# MSP432.net
KiCad netlist of a schematic drawn in Altium Designer
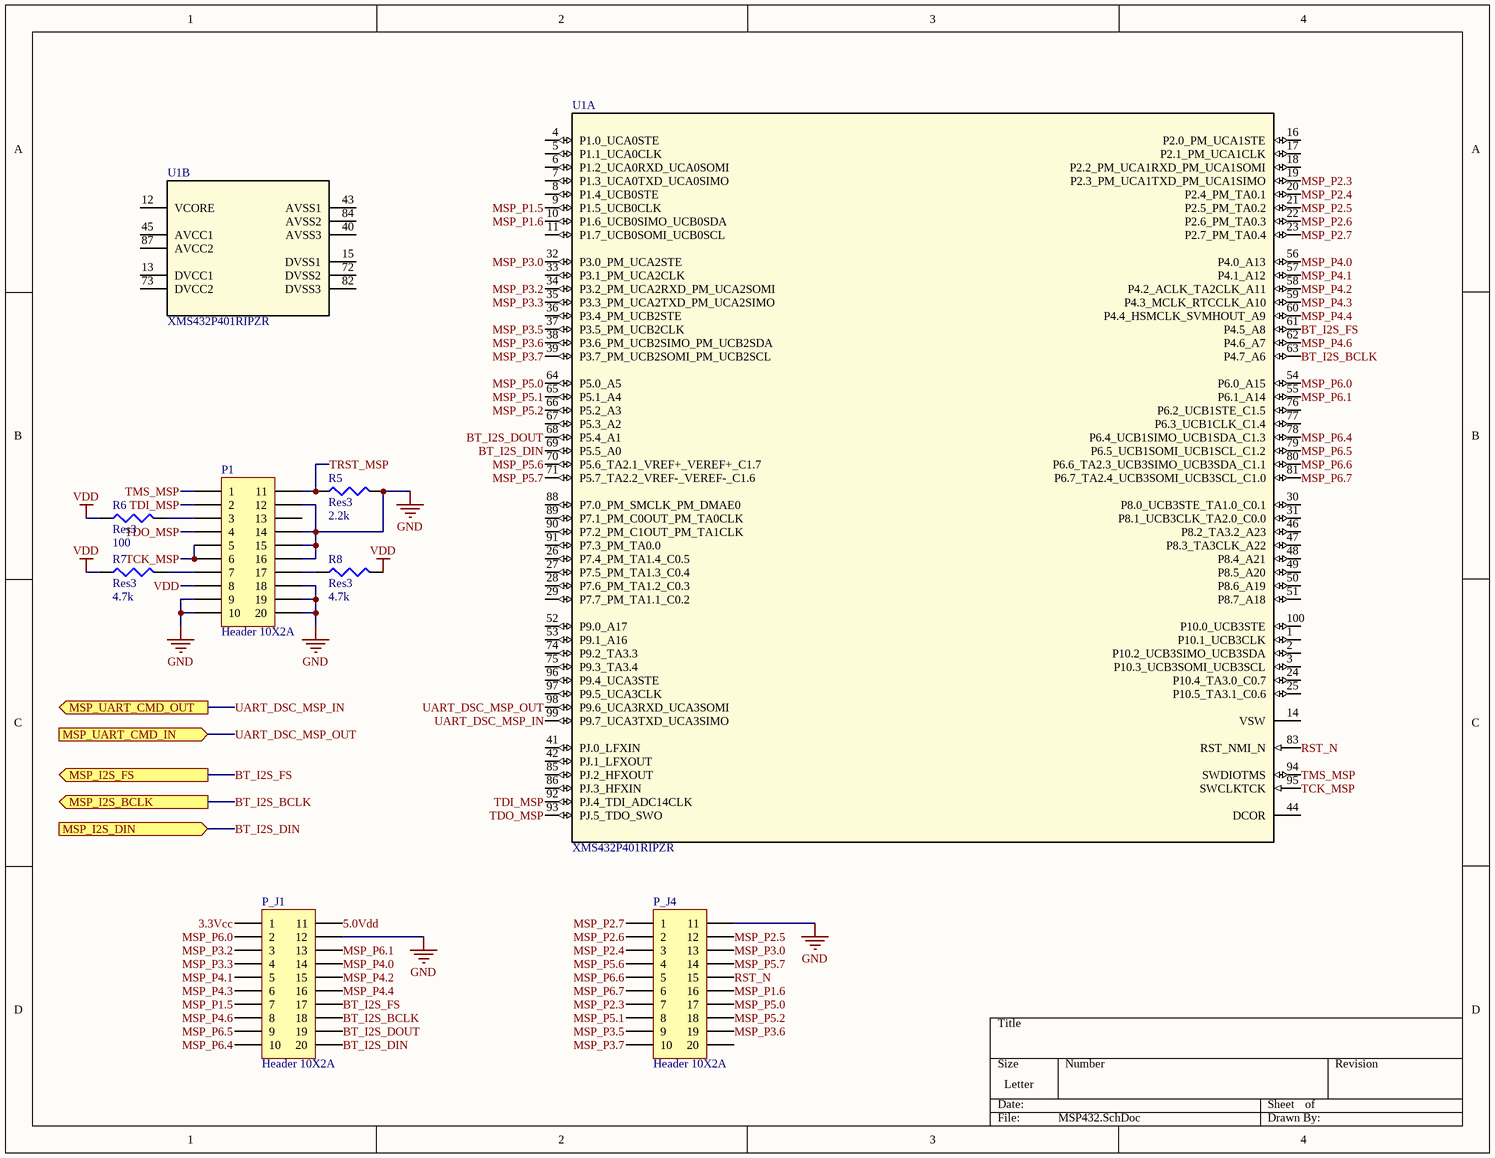
[diagram p0: MSP432.SchDoc]

(export (version "E")
  (design (tool "Eeschema 10.0.6"))
  (components
    (comp (ref "P1")
      (value "Header 10X2A")
      (footprint "HDR2X10_CEN")
      (description "Header, 10-Pin, Dual row")
      (fields (field (name "PUBLISHER") "Altium Limited"))
      (libsource (lib "Miscellaneous Connectors") (part "Header 10X2A"))
    )
    (comp (ref "P_J1")
      (value "Header 10X2A")
      (footprint "HDR2X10_CEN")
      (description "Header, 10-Pin, Dual row")
      (fields (field (name "PUBLISHER") "Altium Limited"))
      (libsource (lib "Miscellaneous Connectors") (part "Header 10X2A"))
    )
    (comp (ref "P_J4")
      (value "Header 10X2A")
      (footprint "HDR2X10_CEN")
      (description "Header, 10-Pin, Dual row")
      (fields (field (name "PUBLISHER") "Altium Limited"))
      (libsource (lib "Miscellaneous Connectors") (part "Header 10X2A"))
    )
    (comp (ref "R5")
      (value "Res3")
      (footprint "J1-0603")
      (description "Resistor")
      (fields (field (name "ALTIUM_VALUE") "2.2k") (field (name "PUBLISHER") "Altium Limited"))
      (libsource (lib "Miscellaneous Devices") (part "Res3"))
    )
    (comp (ref "R6")
      (value "Res3")
      (footprint "J1-0603")
      (description "Resistor")
      (fields (field (name "ALTIUM_VALUE") "100") (field (name "PUBLISHER") "Altium Limited"))
      (libsource (lib "Miscellaneous Devices") (part "Res3"))
    )
    (comp (ref "R7")
      (value "Res3")
      (footprint "J1-0603")
      (description "Resistor")
      (fields (field (name "ALTIUM_VALUE") "4.7k") (field (name "PUBLISHER") "Altium Limited"))
      (libsource (lib "Miscellaneous Devices") (part "Res3"))
    )
    (comp (ref "R8")
      (value "Res3")
      (footprint "J1-0603")
      (description "Resistor")
      (fields (field (name "ALTIUM_VALUE") "4.7k") (field (name "PUBLISHER") "Altium Limited"))
      (libsource (lib "Miscellaneous Devices") (part "Res3"))
    )
    (comp (ref "U1")
      (value "XMS432P401RIPZR")
      (footprint "PZ0100A_N")
      (description "Imported")
      (fields (field (name "MANUFACTURER") "Texas Instruments"))
      (libsource (lib "XMS432P401R") (part "XMS432P401RIPZR"))
    )
  )
  (nets
    (net (code "1") (name "/3.3Vcc") (class "Default")
      (node (ref "P_J1") (pin "1") (pinfunction "1_1") (pintype "passive"))
    )
    (net (code "2") (name "/5.0Vdd") (class "Default")
      (node (ref "P_J1") (pin "11") (pinfunction "11_11") (pintype "passive"))
    )
    (net (code "3") (name "/BT_I2S_BCLK") (class "Default")
      (node (ref "P_J1") (pin "18") (pinfunction "18_18") (pintype "passive"))
      (node (ref "U1") (pin "63") (pinfunction "P4.7_A6_63") (pintype "bidirectional"))
    )
    (net (code "4") (name "/BT_I2S_DIN") (class "Default")
      (node (ref "P_J1") (pin "20") (pinfunction "20_20") (pintype "passive"))
      (node (ref "U1") (pin "69") (pinfunction "P5.5_A0_69") (pintype "bidirectional"))
    )
    (net (code "5") (name "/BT_I2S_DOUT") (class "Default")
      (node (ref "P_J1") (pin "19") (pinfunction "19_19") (pintype "passive"))
      (node (ref "U1") (pin "68") (pinfunction "P5.4_A1_68") (pintype "bidirectional"))
    )
    (net (code "6") (name "/BT_I2S_FS") (class "Default")
      (node (ref "P_J1") (pin "17") (pinfunction "17_17") (pintype "passive"))
      (node (ref "U1") (pin "61") (pinfunction "P4.5_A8_61") (pintype "bidirectional"))
    )
    (net (code "7") (name "/MSP_P1.5") (class "Default")
      (node (ref "P_J1") (pin "7") (pinfunction "7_7") (pintype "passive"))
      (node (ref "U1") (pin "9") (pinfunction "P1.5_UCB0CLK_9") (pintype "bidirectional"))
    )
    (net (code "8") (name "/MSP_P1.6") (class "Default")
      (node (ref "P_J4") (pin "16") (pinfunction "16_16") (pintype "passive"))
      (node (ref "U1") (pin "10") (pinfunction "P1.6_UCB0SIMO_UCB0SDA_10") (pintype "bidirectional"))
    )
    (net (code "9") (name "/MSP_P2.3") (class "Default")
      (node (ref "P_J4") (pin "7") (pinfunction "7_7") (pintype "passive"))
      (node (ref "U1") (pin "19") (pinfunction "P2.3_PM_UCA1TXD_PM_UCA1SIMO_19") (pintype "bidirectional"))
    )
    (net (code "10") (name "/MSP_P2.4") (class "Default")
      (node (ref "P_J4") (pin "3") (pinfunction "3_3") (pintype "passive"))
      (node (ref "U1") (pin "20") (pinfunction "P2.4_PM_TA0.1_20") (pintype "bidirectional"))
    )
    (net (code "11") (name "/MSP_P2.5") (class "Default")
      (node (ref "P_J4") (pin "12") (pinfunction "12_12") (pintype "passive"))
      (node (ref "U1") (pin "21") (pinfunction "P2.5_PM_TA0.2_21") (pintype "bidirectional"))
    )
    (net (code "12") (name "/MSP_P2.6") (class "Default")
      (node (ref "P_J4") (pin "2") (pinfunction "2_2") (pintype "passive"))
      (node (ref "U1") (pin "22") (pinfunction "P2.6_PM_TA0.3_22") (pintype "bidirectional"))
    )
    (net (code "13") (name "/MSP_P2.7") (class "Default")
      (node (ref "P_J4") (pin "1") (pinfunction "1_1") (pintype "passive"))
      (node (ref "U1") (pin "23") (pinfunction "P2.7_PM_TA0.4_23") (pintype "bidirectional"))
    )
    (net (code "14") (name "/MSP_P3.0") (class "Default")
      (node (ref "P_J4") (pin "13") (pinfunction "13_13") (pintype "passive"))
      (node (ref "U1") (pin "32") (pinfunction "P3.0_PM_UCA2STE_32") (pintype "bidirectional"))
    )
    (net (code "15") (name "/MSP_P3.2") (class "Default")
      (node (ref "P_J1") (pin "3") (pinfunction "3_3") (pintype "passive"))
      (node (ref "U1") (pin "34") (pinfunction "P3.2_PM_UCA2RXD_PM_UCA2SOMI_34") (pintype "bidirectional"))
    )
    (net (code "16") (name "/MSP_P3.3") (class "Default")
      (node (ref "P_J1") (pin "4") (pinfunction "4_4") (pintype "passive"))
      (node (ref "U1") (pin "35") (pinfunction "P3.3_PM_UCA2TXD_PM_UCA2SIMO_35") (pintype "bidirectional"))
    )
    (net (code "17") (name "/MSP_P3.5") (class "Default")
      (node (ref "P_J4") (pin "9") (pinfunction "9_9") (pintype "passive"))
      (node (ref "U1") (pin "37") (pinfunction "P3.5_PM_UCB2CLK_37") (pintype "bidirectional"))
    )
    (net (code "18") (name "/MSP_P3.6") (class "Default")
      (node (ref "P_J4") (pin "19") (pinfunction "19_19") (pintype "passive"))
      (node (ref "U1") (pin "38") (pinfunction "P3.6_PM_UCB2SIMO_PM_UCB2SDA_38") (pintype "bidirectional"))
    )
    (net (code "19") (name "/MSP_P3.7") (class "Default")
      (node (ref "P_J4") (pin "10") (pinfunction "10_10") (pintype "passive"))
      (node (ref "U1") (pin "39") (pinfunction "P3.7_PM_UCB2SOMI_PM_UCB2SCL_39") (pintype "bidirectional"))
    )
    (net (code "20") (name "/MSP_P4.0") (class "Default")
      (node (ref "P_J1") (pin "14") (pinfunction "14_14") (pintype "passive"))
      (node (ref "U1") (pin "56") (pinfunction "P4.0_A13_56") (pintype "bidirectional"))
    )
    (net (code "21") (name "/MSP_P4.1") (class "Default")
      (node (ref "P_J1") (pin "5") (pinfunction "5_5") (pintype "passive"))
      (node (ref "U1") (pin "57") (pinfunction "P4.1_A12_57") (pintype "bidirectional"))
    )
    (net (code "22") (name "/MSP_P4.2") (class "Default")
      (node (ref "P_J1") (pin "15") (pinfunction "15_15") (pintype "passive"))
      (node (ref "U1") (pin "58") (pinfunction "P4.2_ACLK_TA2CLK_A11_58") (pintype "bidirectional"))
    )
    (net (code "23") (name "/MSP_P4.3") (class "Default")
      (node (ref "P_J1") (pin "6") (pinfunction "6_6") (pintype "passive"))
      (node (ref "U1") (pin "59") (pinfunction "P4.3_MCLK_RTCCLK_A10_59") (pintype "bidirectional"))
    )
    (net (code "24") (name "/MSP_P4.4") (class "Default")
      (node (ref "P_J1") (pin "16") (pinfunction "16_16") (pintype "passive"))
      (node (ref "U1") (pin "60") (pinfunction "P4.4_HSMCLK_SVMHOUT_A9_60") (pintype "bidirectional"))
    )
    (net (code "25") (name "/MSP_P4.6") (class "Default")
      (node (ref "P_J1") (pin "8") (pinfunction "8_8") (pintype "passive"))
      (node (ref "U1") (pin "62") (pinfunction "P4.6_A7_62") (pintype "bidirectional"))
    )
    (net (code "26") (name "/MSP_P5.0") (class "Default")
      (node (ref "P_J4") (pin "17") (pinfunction "17_17") (pintype "passive"))
      (node (ref "U1") (pin "64") (pinfunction "P5.0_A5_64") (pintype "bidirectional"))
    )
    (net (code "27") (name "/MSP_P5.1") (class "Default")
      (node (ref "P_J4") (pin "8") (pinfunction "8_8") (pintype "passive"))
      (node (ref "U1") (pin "65") (pinfunction "P5.1_A4_65") (pintype "bidirectional"))
    )
    (net (code "28") (name "/MSP_P5.2") (class "Default")
      (node (ref "P_J4") (pin "18") (pinfunction "18_18") (pintype "passive"))
      (node (ref "U1") (pin "66") (pinfunction "P5.2_A3_66") (pintype "bidirectional"))
    )
    (net (code "29") (name "/MSP_P5.6") (class "Default")
      (node (ref "P_J4") (pin "4") (pinfunction "4_4") (pintype "passive"))
      (node (ref "U1") (pin "70") (pinfunction "P5.6_TA2.1_VREF+_VEREF+_C1.7_70") (pintype "bidirectional"))
    )
    (net (code "30") (name "/MSP_P5.7") (class "Default")
      (node (ref "P_J4") (pin "14") (pinfunction "14_14") (pintype "passive"))
      (node (ref "U1") (pin "71") (pinfunction "P5.7_TA2.2_VREF-_VEREF-_C1.6_71") (pintype "bidirectional"))
    )
    (net (code "31") (name "/MSP_P6.0") (class "Default")
      (node (ref "P_J1") (pin "2") (pinfunction "2_2") (pintype "passive"))
      (node (ref "U1") (pin "54") (pinfunction "P6.0_A15_54") (pintype "bidirectional"))
    )
    (net (code "32") (name "/MSP_P6.1") (class "Default")
      (node (ref "P_J1") (pin "13") (pinfunction "13_13") (pintype "passive"))
      (node (ref "U1") (pin "55") (pinfunction "P6.1_A14_55") (pintype "bidirectional"))
    )
    (net (code "33") (name "/MSP_P6.4") (class "Default")
      (node (ref "P_J1") (pin "10") (pinfunction "10_10") (pintype "passive"))
      (node (ref "U1") (pin "78") (pinfunction "P6.4_UCB1SIMO_UCB1SDA_C1.3_78") (pintype "bidirectional"))
    )
    (net (code "34") (name "/MSP_P6.5") (class "Default")
      (node (ref "P_J1") (pin "9") (pinfunction "9_9") (pintype "passive"))
      (node (ref "U1") (pin "79") (pinfunction "P6.5_UCB1SOMI_UCB1SCL_C1.2_79") (pintype "bidirectional"))
    )
    (net (code "35") (name "/MSP_P6.6") (class "Default")
      (node (ref "P_J4") (pin "5") (pinfunction "5_5") (pintype "passive"))
      (node (ref "U1") (pin "80") (pinfunction "P6.6_TA2.3_UCB3SIMO_UCB3SDA_C1.1_80") (pintype "bidirectional"))
    )
    (net (code "36") (name "/MSP_P6.7") (class "Default")
      (node (ref "P_J4") (pin "6") (pinfunction "6_6") (pintype "passive"))
      (node (ref "U1") (pin "81") (pinfunction "P6.7_TA2.4_UCB3SOMI_UCB3SCL_C1.0_81") (pintype "bidirectional"))
    )
    (net (code "37") (name "/RST_N") (class "Default")
      (node (ref "P_J4") (pin "15") (pinfunction "15_15") (pintype "passive"))
      (node (ref "U1") (pin "83") (pinfunction "RST_NMI_N_83") (pintype "input"))
    )
    (net (code "38") (name "/TCK_MSP") (class "Default")
      (node (ref "P1") (pin "5") (pinfunction "5_5") (pintype "passive"))
      (node (ref "P1") (pin "6") (pinfunction "6_6") (pintype "passive"))
      (node (ref "U1") (pin "95") (pinfunction "SWCLKTCK_95") (pintype "input"))
    )
    (net (code "39") (name "/TDI_MSP") (class "Default")
      (node (ref "P1") (pin "2") (pinfunction "2_2") (pintype "passive"))
      (node (ref "U1") (pin "92") (pinfunction "PJ.4_TDI_ADC14CLK_92") (pintype "bidirectional"))
    )
    (net (code "40") (name "/TDO_MSP") (class "Default")
      (node (ref "P1") (pin "4") (pinfunction "4_4") (pintype "passive"))
      (node (ref "U1") (pin "93") (pinfunction "PJ.5_TDO_SWO_93") (pintype "bidirectional"))
    )
    (net (code "41") (name "/TMS_MSP") (class "Default")
      (node (ref "P1") (pin "1") (pinfunction "1_1") (pintype "passive"))
      (node (ref "U1") (pin "94") (pinfunction "SWDIOTMS_94") (pintype "bidirectional"))
    )
    (net (code "42") (name "/TRST_MSP") (class "Default")
      (node (ref "P1") (pin "11") (pinfunction "11_11") (pintype "passive"))
      (node (ref "R5") (pin "1") (pinfunction "1_1") (pintype "passive"))
    )
    (net (code "43") (name "/UART_DSC_MSP_IN") (class "Default")
      (node (ref "U1") (pin "99") (pinfunction "P9.7_UCA3TXD_UCA3SIMO_99") (pintype "bidirectional"))
    )
    (net (code "44") (name "/UART_DSC_MSP_OUT") (class "Default")
      (node (ref "U1") (pin "98") (pinfunction "P9.6_UCA3RXD_UCA3SOMI_98") (pintype "bidirectional"))
    )
    (net (code "45") (name "GND") (class "Default")
      (node (ref "P1") (pin "10") (pinfunction "10_10") (pintype "passive"))
      (node (ref "P1") (pin "12") (pinfunction "12_12") (pintype "passive"))
      (node (ref "P1") (pin "14") (pinfunction "14_14") (pintype "passive"))
      (node (ref "P1") (pin "15") (pinfunction "15_15") (pintype "passive"))
      (node (ref "P1") (pin "16") (pinfunction "16_16") (pintype "passive"))
      (node (ref "P1") (pin "18") (pinfunction "18_18") (pintype "passive"))
      (node (ref "P1") (pin "19") (pinfunction "19_19") (pintype "passive"))
      (node (ref "P1") (pin "20") (pinfunction "20_20") (pintype "passive"))
      (node (ref "P1") (pin "9") (pinfunction "9_9") (pintype "passive"))
      (node (ref "P_J1") (pin "12") (pinfunction "12_12") (pintype "passive"))
      (node (ref "P_J4") (pin "11") (pinfunction "11_11") (pintype "passive"))
      (node (ref "R5") (pin "2") (pinfunction "2_2") (pintype "passive"))
    )
    (net (code "46") (name "Net-(P1-Pad3)") (class "Default")
      (node (ref "P1") (pin "3") (pinfunction "3_3") (pintype "passive"))
      (node (ref "R6") (pin "2") (pinfunction "2_2") (pintype "passive"))
    )
    (net (code "47") (name "Net-(P1-Pad7)") (class "Default")
      (node (ref "P1") (pin "7") (pinfunction "7_7") (pintype "passive"))
      (node (ref "R7") (pin "2") (pinfunction "2_2") (pintype "passive"))
    )
    (net (code "48") (name "Net-(P1-Pad17)") (class "Default")
      (node (ref "P1") (pin "17") (pinfunction "17_17") (pintype "passive"))
      (node (ref "R8") (pin "1") (pinfunction "1_1") (pintype "passive"))
    )
    (net (code "49") (name "VDD") (class "Default")
      (node (ref "P1") (pin "8") (pinfunction "8_8") (pintype "passive"))
      (node (ref "R6") (pin "1") (pinfunction "1_1") (pintype "passive"))
      (node (ref "R7") (pin "1") (pinfunction "1_1") (pintype "passive"))
      (node (ref "R8") (pin "2") (pinfunction "2_2") (pintype "passive"))
    )
    (net (code "50") (name "unconnected-(P1-Pad13)") (class "Default")
      (node (ref "P1") (pin "13") (pinfunction "13_13") (pintype "passive"))
    )
    (net (code "51") (name "unconnected-(P_J4-Pad20)") (class "Default")
      (node (ref "P_J4") (pin "20") (pinfunction "20_20") (pintype "passive"))
    )
    (net (code "52") (name "unconnected-(U1A-DCOR-Pad44)") (class "Default")
      (node (ref "U1") (pin "44") (pinfunction "DCOR_44") (pintype "passive"))
    )
    (net (code "53") (name "unconnected-(U1A-P1.0_UCA0STE-Pad4)") (class "Default")
      (node (ref "U1") (pin "4") (pinfunction "P1.0_UCA0STE_4") (pintype "bidirectional"))
    )
    (net (code "54") (name "unconnected-(U1A-P1.1_UCA0CLK-Pad5)") (class "Default")
      (node (ref "U1") (pin "5") (pinfunction "P1.1_UCA0CLK_5") (pintype "bidirectional"))
    )
    (net (code "55") (name "unconnected-(U1A-P1.2_UCA0RXD_UCA0SOMI-Pad6)") (class "Default")
      (node (ref "U1") (pin "6") (pinfunction "P1.2_UCA0RXD_UCA0SOMI_6") (pintype "bidirectional"))
    )
    (net (code "56") (name "unconnected-(U1A-P1.3_UCA0TXD_UCA0SIMO-Pad7)") (class "Default")
      (node (ref "U1") (pin "7") (pinfunction "P1.3_UCA0TXD_UCA0SIMO_7") (pintype "bidirectional"))
    )
    (net (code "57") (name "unconnected-(U1A-P1.4_UCB0STE-Pad8)") (class "Default")
      (node (ref "U1") (pin "8") (pinfunction "P1.4_UCB0STE_8") (pintype "bidirectional"))
    )
    (net (code "58") (name "unconnected-(U1A-P1.7_UCB0SOMI_UCB0SCL-Pad11)") (class "Default")
      (node (ref "U1") (pin "11") (pinfunction "P1.7_UCB0SOMI_UCB0SCL_11") (pintype "bidirectional"))
    )
    (net (code "59") (name "unconnected-(U1A-P2.0_PM_UCA1STE-Pad16)") (class "Default")
      (node (ref "U1") (pin "16") (pinfunction "P2.0_PM_UCA1STE_16") (pintype "bidirectional"))
    )
    (net (code "60") (name "unconnected-(U1A-P2.1_PM_UCA1CLK-Pad17)") (class "Default")
      (node (ref "U1") (pin "17") (pinfunction "P2.1_PM_UCA1CLK_17") (pintype "bidirectional"))
    )
    (net (code "61") (name "unconnected-(U1A-P2.2_PM_UCA1RXD_PM_UCA1SOMI-Pad18)") (class "Default")
      (node (ref "U1") (pin "18") (pinfunction "P2.2_PM_UCA1RXD_PM_UCA1SOMI_18") (pintype "bidirectional"))
    )
    (net (code "62") (name "unconnected-(U1A-P3.1_PM_UCA2CLK-Pad33)") (class "Default")
      (node (ref "U1") (pin "33") (pinfunction "P3.1_PM_UCA2CLK_33") (pintype "bidirectional"))
    )
    (net (code "63") (name "unconnected-(U1A-P3.4_PM_UCB2STE-Pad36)") (class "Default")
      (node (ref "U1") (pin "36") (pinfunction "P3.4_PM_UCB2STE_36") (pintype "bidirectional"))
    )
    (net (code "64") (name "unconnected-(U1A-P5.3_A2-Pad67)") (class "Default")
      (node (ref "U1") (pin "67") (pinfunction "P5.3_A2_67") (pintype "bidirectional"))
    )
    (net (code "65") (name "unconnected-(U1A-P6.2_UCB1STE_C1.5-Pad76)") (class "Default")
      (node (ref "U1") (pin "76") (pinfunction "P6.2_UCB1STE_C1.5_76") (pintype "bidirectional"))
    )
    (net (code "66") (name "unconnected-(U1A-P6.3_UCB1CLK_C1.4-Pad77)") (class "Default")
      (node (ref "U1") (pin "77") (pinfunction "P6.3_UCB1CLK_C1.4_77") (pintype "bidirectional"))
    )
    (net (code "67") (name "unconnected-(U1A-P7.0_PM_SMCLK_PM_DMAE0-Pad88)") (class "Default")
      (node (ref "U1") (pin "88") (pinfunction "P7.0_PM_SMCLK_PM_DMAE0_88") (pintype "bidirectional"))
    )
    (net (code "68") (name "unconnected-(U1A-P7.1_PM_C0OUT_PM_TA0CLK-Pad89)") (class "Default")
      (node (ref "U1") (pin "89") (pinfunction "P7.1_PM_C0OUT_PM_TA0CLK_89") (pintype "bidirectional"))
    )
    (net (code "69") (name "unconnected-(U1A-P7.2_PM_C1OUT_PM_TA1CLK-Pad90)") (class "Default")
      (node (ref "U1") (pin "90") (pinfunction "P7.2_PM_C1OUT_PM_TA1CLK_90") (pintype "bidirectional"))
    )
    (net (code "70") (name "unconnected-(U1A-P7.3_PM_TA0.0-Pad91)") (class "Default")
      (node (ref "U1") (pin "91") (pinfunction "P7.3_PM_TA0.0_91") (pintype "bidirectional"))
    )
    (net (code "71") (name "unconnected-(U1A-P7.4_PM_TA1.4_C0.5-Pad26)") (class "Default")
      (node (ref "U1") (pin "26") (pinfunction "P7.4_PM_TA1.4_C0.5_26") (pintype "bidirectional"))
    )
    (net (code "72") (name "unconnected-(U1A-P7.5_PM_TA1.3_C0.4-Pad27)") (class "Default")
      (node (ref "U1") (pin "27") (pinfunction "P7.5_PM_TA1.3_C0.4_27") (pintype "bidirectional"))
    )
    (net (code "73") (name "unconnected-(U1A-P7.6_PM_TA1.2_C0.3-Pad28)") (class "Default")
      (node (ref "U1") (pin "28") (pinfunction "P7.6_PM_TA1.2_C0.3_28") (pintype "bidirectional"))
    )
    (net (code "74") (name "unconnected-(U1A-P7.7_PM_TA1.1_C0.2-Pad29)") (class "Default")
      (node (ref "U1") (pin "29") (pinfunction "P7.7_PM_TA1.1_C0.2_29") (pintype "bidirectional"))
    )
    (net (code "75") (name "unconnected-(U1A-P8.0_UCB3STE_TA1.0_C0.1-Pad30)") (class "Default")
      (node (ref "U1") (pin "30") (pinfunction "P8.0_UCB3STE_TA1.0_C0.1_30") (pintype "bidirectional"))
    )
    (net (code "76") (name "unconnected-(U1A-P8.1_UCB3CLK_TA2.0_C0.0-Pad31)") (class "Default")
      (node (ref "U1") (pin "31") (pinfunction "P8.1_UCB3CLK_TA2.0_C0.0_31") (pintype "bidirectional"))
    )
    (net (code "77") (name "unconnected-(U1A-P8.2_TA3.2_A23-Pad46)") (class "Default")
      (node (ref "U1") (pin "46") (pinfunction "P8.2_TA3.2_A23_46") (pintype "bidirectional"))
    )
    (net (code "78") (name "unconnected-(U1A-P8.3_TA3CLK_A22-Pad47)") (class "Default")
      (node (ref "U1") (pin "47") (pinfunction "P8.3_TA3CLK_A22_47") (pintype "bidirectional"))
    )
    (net (code "79") (name "unconnected-(U1A-P8.4_A21-Pad48)") (class "Default")
      (node (ref "U1") (pin "48") (pinfunction "P8.4_A21_48") (pintype "bidirectional"))
    )
    (net (code "80") (name "unconnected-(U1A-P8.5_A20-Pad49)") (class "Default")
      (node (ref "U1") (pin "49") (pinfunction "P8.5_A20_49") (pintype "bidirectional"))
    )
    (net (code "81") (name "unconnected-(U1A-P8.6_A19-Pad50)") (class "Default")
      (node (ref "U1") (pin "50") (pinfunction "P8.6_A19_50") (pintype "bidirectional"))
    )
    (net (code "82") (name "unconnected-(U1A-P8.7_A18-Pad51)") (class "Default")
      (node (ref "U1") (pin "51") (pinfunction "P8.7_A18_51") (pintype "bidirectional"))
    )
    (net (code "83") (name "unconnected-(U1A-P9.0_A17-Pad52)") (class "Default")
      (node (ref "U1") (pin "52") (pinfunction "P9.0_A17_52") (pintype "bidirectional"))
    )
    (net (code "84") (name "unconnected-(U1A-P9.1_A16-Pad53)") (class "Default")
      (node (ref "U1") (pin "53") (pinfunction "P9.1_A16_53") (pintype "bidirectional"))
    )
    (net (code "85") (name "unconnected-(U1A-P9.2_TA3.3-Pad74)") (class "Default")
      (node (ref "U1") (pin "74") (pinfunction "P9.2_TA3.3_74") (pintype "bidirectional"))
    )
    (net (code "86") (name "unconnected-(U1A-P9.3_TA3.4-Pad75)") (class "Default")
      (node (ref "U1") (pin "75") (pinfunction "P9.3_TA3.4_75") (pintype "bidirectional"))
    )
    (net (code "87") (name "unconnected-(U1A-P9.4_UCA3STE-Pad96)") (class "Default")
      (node (ref "U1") (pin "96") (pinfunction "P9.4_UCA3STE_96") (pintype "bidirectional"))
    )
    (net (code "88") (name "unconnected-(U1A-P9.5_UCA3CLK-Pad97)") (class "Default")
      (node (ref "U1") (pin "97") (pinfunction "P9.5_UCA3CLK_97") (pintype "bidirectional"))
    )
    (net (code "89") (name "unconnected-(U1A-P10.0_UCB3STE-Pad100)") (class "Default")
      (node (ref "U1") (pin "100") (pinfunction "P10.0_UCB3STE_100") (pintype "bidirectional"))
    )
    (net (code "90") (name "unconnected-(U1A-P10.1_UCB3CLK-Pad1)") (class "Default")
      (node (ref "U1") (pin "1") (pinfunction "P10.1_UCB3CLK_1") (pintype "bidirectional"))
    )
    (net (code "91") (name "unconnected-(U1A-P10.2_UCB3SIMO_UCB3SDA-Pad2)") (class "Default")
      (node (ref "U1") (pin "2") (pinfunction "P10.2_UCB3SIMO_UCB3SDA_2") (pintype "bidirectional"))
    )
    (net (code "92") (name "unconnected-(U1A-P10.3_UCB3SOMI_UCB3SCL-Pad3)") (class "Default")
      (node (ref "U1") (pin "3") (pinfunction "P10.3_UCB3SOMI_UCB3SCL_3") (pintype "bidirectional"))
    )
    (net (code "93") (name "unconnected-(U1A-P10.4_TA3.0_C0.7-Pad24)") (class "Default")
      (node (ref "U1") (pin "24") (pinfunction "P10.4_TA3.0_C0.7_24") (pintype "bidirectional"))
    )
    (net (code "94") (name "unconnected-(U1A-P10.5_TA3.1_C0.6-Pad25)") (class "Default")
      (node (ref "U1") (pin "25") (pinfunction "P10.5_TA3.1_C0.6_25") (pintype "bidirectional"))
    )
    (net (code "95") (name "unconnected-(U1A-PJ.0_LFXIN-Pad41)") (class "Default")
      (node (ref "U1") (pin "41") (pinfunction "PJ.0_LFXIN_41") (pintype "bidirectional"))
    )
    (net (code "96") (name "unconnected-(U1A-PJ.1_LFXOUT-Pad42)") (class "Default")
      (node (ref "U1") (pin "42") (pinfunction "PJ.1_LFXOUT_42") (pintype "bidirectional"))
    )
    (net (code "97") (name "unconnected-(U1A-PJ.2_HFXOUT-Pad85)") (class "Default")
      (node (ref "U1") (pin "85") (pinfunction "PJ.2_HFXOUT_85") (pintype "bidirectional"))
    )
    (net (code "98") (name "unconnected-(U1A-PJ.3_HFXIN-Pad86)") (class "Default")
      (node (ref "U1") (pin "86") (pinfunction "PJ.3_HFXIN_86") (pintype "bidirectional"))
    )
    (net (code "99") (name "unconnected-(U1A-VSW-Pad14)") (class "Default")
      (node (ref "U1") (pin "14") (pinfunction "VSW_14") (pintype "passive"))
    )
    (net (code "100") (name "unconnected-(U1B-AVCC1-Pad45)") (class "Default")
      (node (ref "U1") (pin "45") (pinfunction "AVCC1_45") (pintype "power_in"))
    )
    (net (code "101") (name "unconnected-(U1B-AVCC2-Pad87)") (class "Default")
      (node (ref "U1") (pin "87") (pinfunction "AVCC2_87") (pintype "power_in"))
    )
    (net (code "102") (name "unconnected-(U1B-AVSS1-Pad43)") (class "Default")
      (node (ref "U1") (pin "43") (pinfunction "AVSS1_43") (pintype "power_in"))
    )
    (net (code "103") (name "unconnected-(U1B-AVSS2-Pad84)") (class "Default")
      (node (ref "U1") (pin "84") (pinfunction "AVSS2_84") (pintype "power_in"))
    )
    (net (code "104") (name "unconnected-(U1B-AVSS3-Pad40)") (class "Default")
      (node (ref "U1") (pin "40") (pinfunction "AVSS3_40") (pintype "power_in"))
    )
    (net (code "105") (name "unconnected-(U1B-DVCC1-Pad13)") (class "Default")
      (node (ref "U1") (pin "13") (pinfunction "DVCC1_13") (pintype "power_in"))
    )
    (net (code "106") (name "unconnected-(U1B-DVCC2-Pad73)") (class "Default")
      (node (ref "U1") (pin "73") (pinfunction "DVCC2_73") (pintype "power_in"))
    )
    (net (code "107") (name "unconnected-(U1B-DVSS1-Pad15)") (class "Default")
      (node (ref "U1") (pin "15") (pinfunction "DVSS1_15") (pintype "power_in"))
    )
    (net (code "108") (name "unconnected-(U1B-DVSS2-Pad72)") (class "Default")
      (node (ref "U1") (pin "72") (pinfunction "DVSS2_72") (pintype "power_in"))
    )
    (net (code "109") (name "unconnected-(U1B-DVSS3-Pad82)") (class "Default")
      (node (ref "U1") (pin "82") (pinfunction "DVSS3_82") (pintype "power_in"))
    )
    (net (code "110") (name "unconnected-(U1B-VCORE-Pad12)") (class "Default")
      (node (ref "U1") (pin "12") (pinfunction "VCORE_12") (pintype "power_in"))
    )
  )
)
